# CAMERA_INTERFACE.net
KiCad netlist of a schematic drawn in Altium Designer
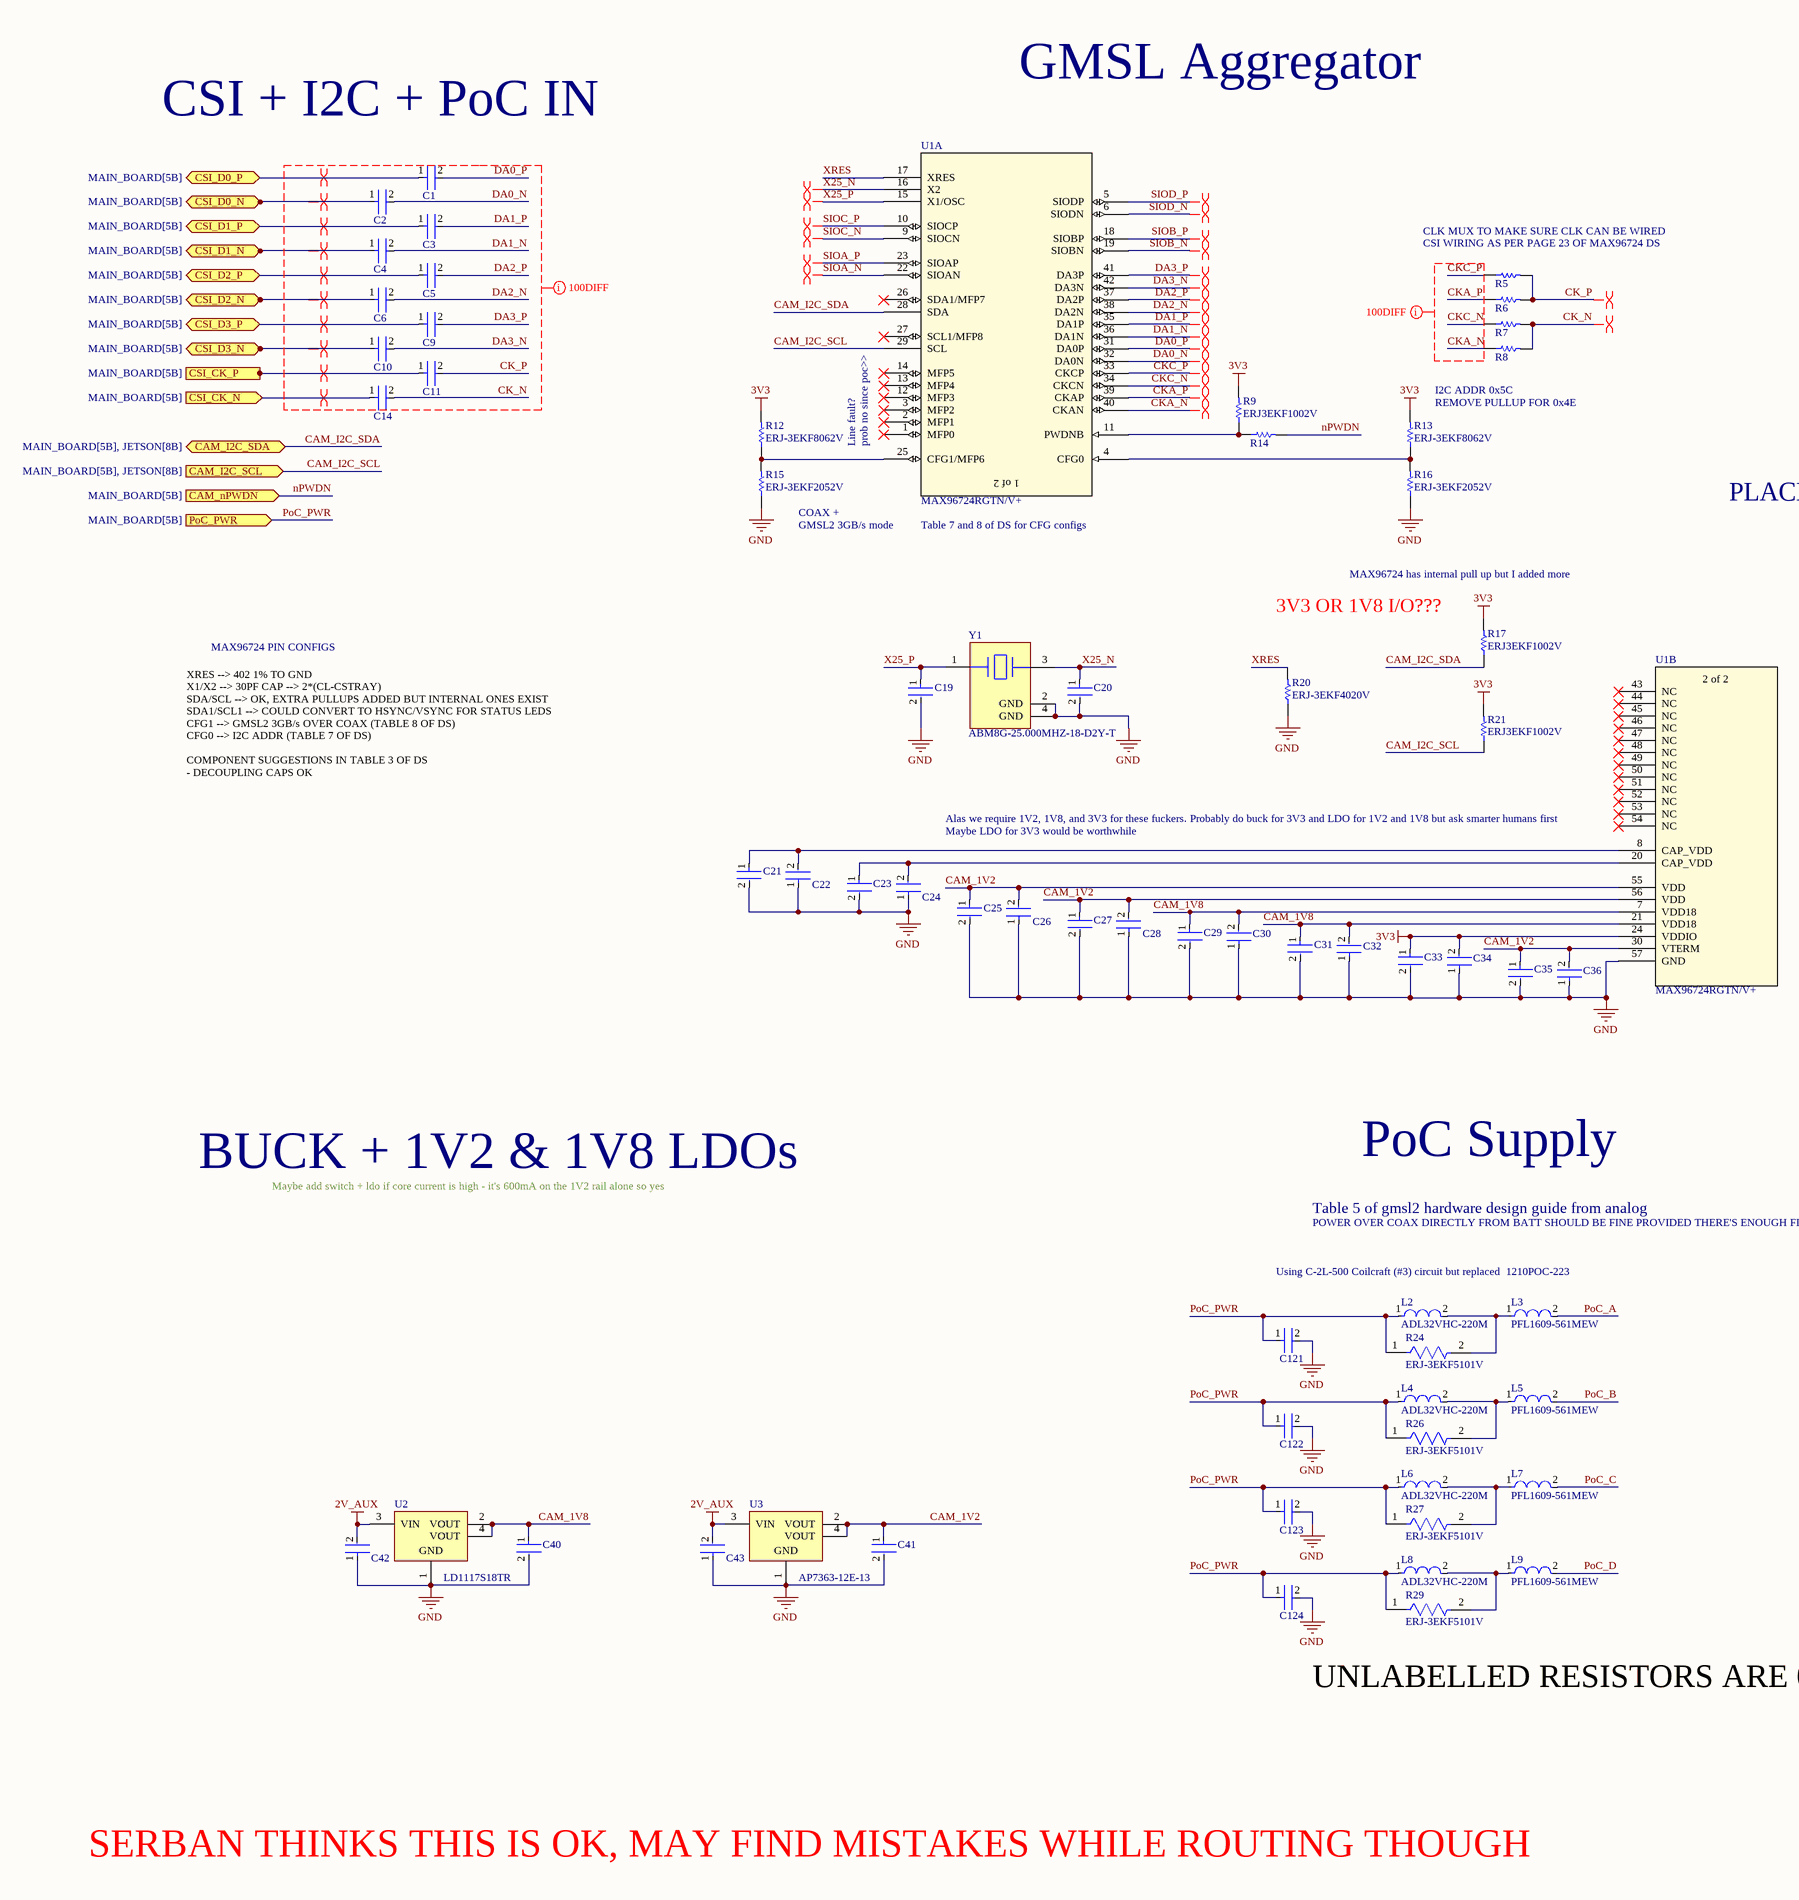
[diagram p0: CAMERA_INTERFACE.SchDoc, left]
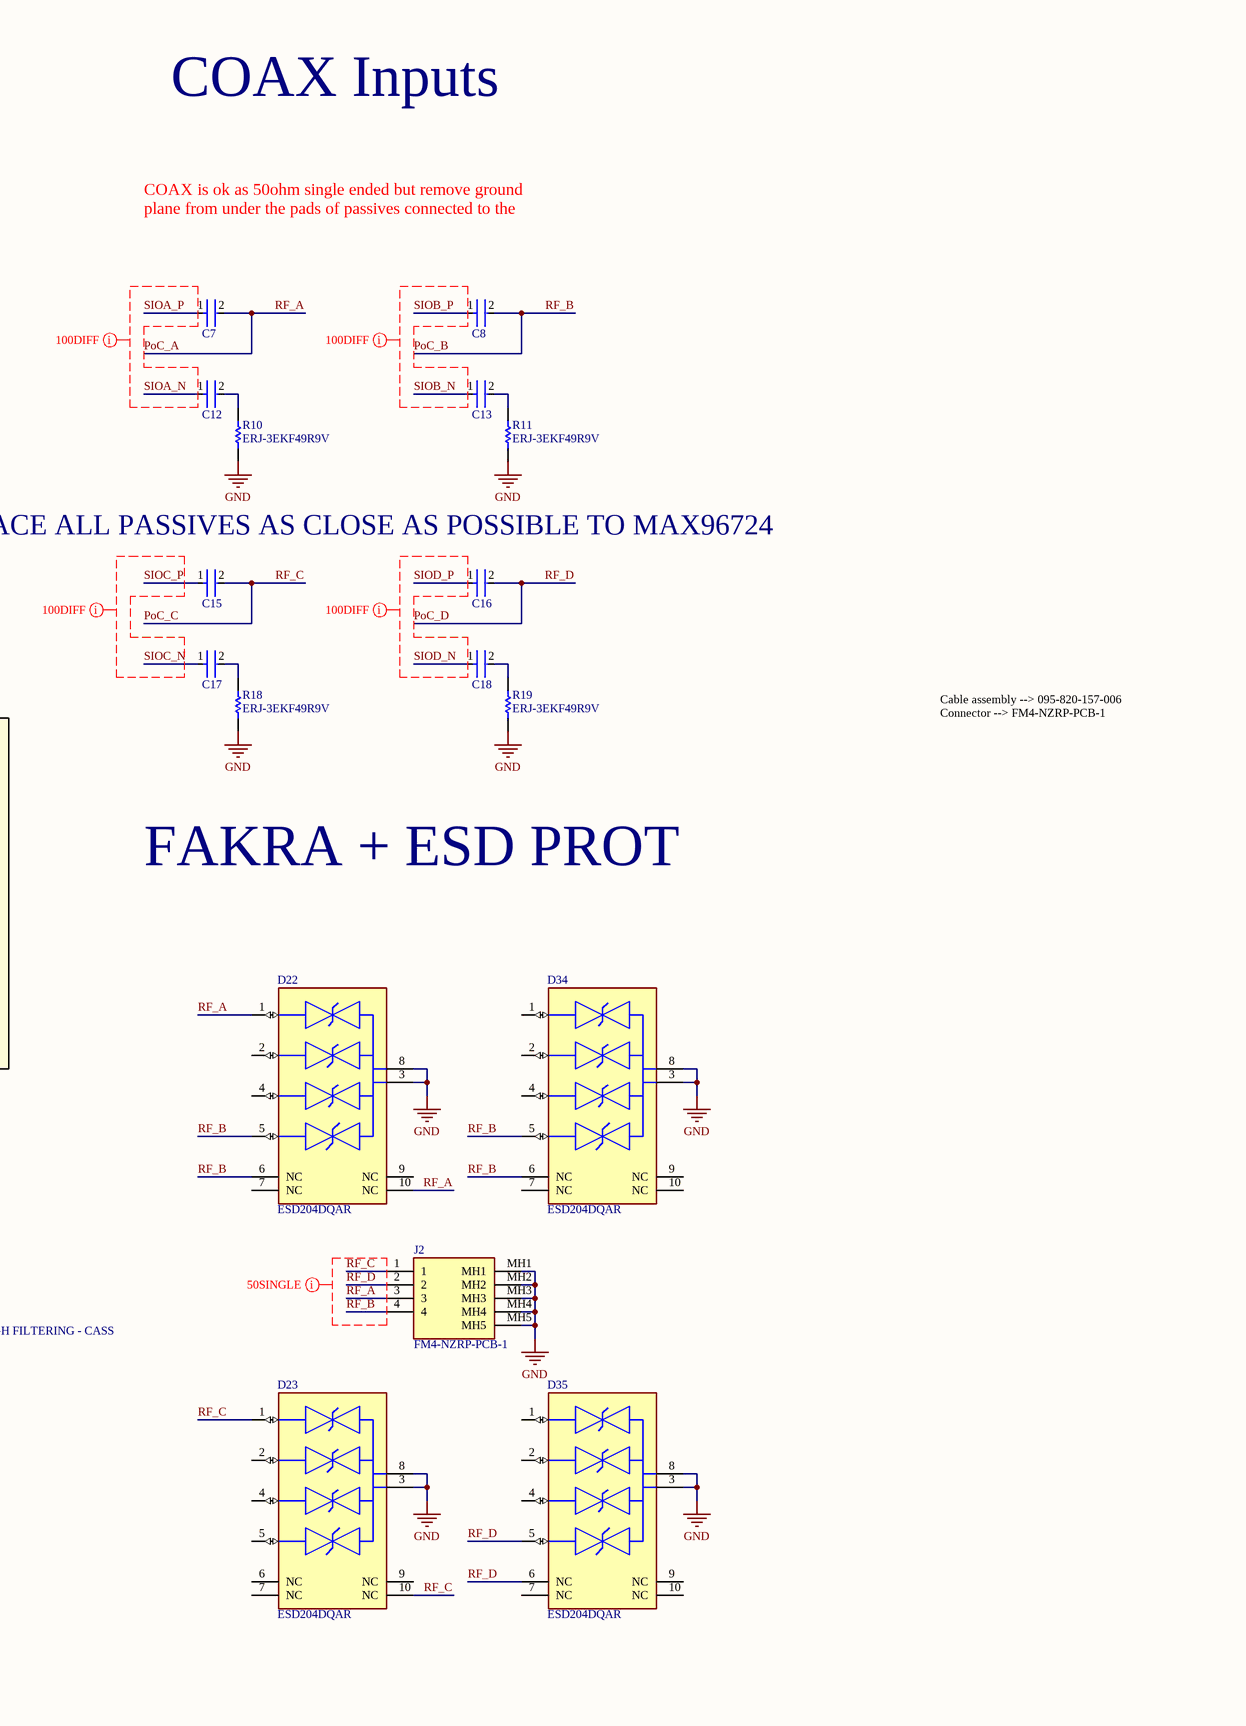
[diagram p1: CAMERA_INTERFACE.SchDoc, right]

(export (version "E")
  (design (tool "Eeschema 10.0.6"))
  (components
    (comp (ref "C1")
      (value "C1005X7R1H104K050BB")
      (footprint "FP-C1005-050-0_05-IPC_C")
      (description "Multilayer Ceramic Capacitors 100nF ±10% 50V X7R SMD 0402")
      (fields (field (name "VOLTAGE") "50V") (field (name "TOLERANCE") "10%"))
      (libsource (lib "Altium Content Vault") (part "b4654b650e69147ec39a6b967a45e02"))
    )
    (comp (ref "C2")
      (value "C1005X7R1H104K050BB")
      (footprint "FP-C1005-050-0_05-IPC_C")
      (description "Multilayer Ceramic Capacitors 100nF ±10% 50V X7R SMD 0402")
      (fields (field (name "VOLTAGE") "50V") (field (name "TOLERANCE") "10%"))
      (libsource (lib "Altium Content Vault") (part "b4654b650e69147ec39a6b967a45e02"))
    )
    (comp (ref "C3")
      (value "C1005X7R1H104K050BB")
      (footprint "FP-C1005-050-0_05-IPC_C")
      (description "Multilayer Ceramic Capacitors 100nF ±10% 50V X7R SMD 0402")
      (fields (field (name "VOLTAGE") "50V") (field (name "TOLERANCE") "10%"))
      (libsource (lib "Altium Content Vault") (part "b4654b650e69147ec39a6b967a45e02"))
    )
    (comp (ref "C4")
      (value "C1005X7R1H104K050BB")
      (footprint "FP-C1005-050-0_05-IPC_C")
      (description "Multilayer Ceramic Capacitors 100nF ±10% 50V X7R SMD 0402")
      (fields (field (name "VOLTAGE") "50V") (field (name "TOLERANCE") "10%"))
      (libsource (lib "Altium Content Vault") (part "b4654b650e69147ec39a6b967a45e02"))
    )
    (comp (ref "C5")
      (value "C1005X7R1H104K050BB")
      (footprint "FP-C1005-050-0_05-IPC_C")
      (description "Multilayer Ceramic Capacitors 100nF ±10% 50V X7R SMD 0402")
      (fields (field (name "VOLTAGE") "50V") (field (name "TOLERANCE") "10%"))
      (libsource (lib "Altium Content Vault") (part "b4654b650e69147ec39a6b967a45e02"))
    )
    (comp (ref "C6")
      (value "C1005X7R1H104K050BB")
      (footprint "FP-C1005-050-0_05-IPC_C")
      (description "Multilayer Ceramic Capacitors 100nF ±10% 50V X7R SMD 0402")
      (fields (field (name "VOLTAGE") "50V") (field (name "TOLERANCE") "10%"))
      (libsource (lib "Altium Content Vault") (part "b4654b650e69147ec39a6b967a45e02"))
    )
    (comp (ref "C7")
      (value "C1005X7R1H104K050BB")
      (footprint "FP-C1005-050-0_05-IPC_C")
      (description "Multilayer Ceramic Capacitors 100nF ±10% 50V X7R SMD 0402")
      (fields (field (name "VOLTAGE") "50V") (field (name "TOLERANCE") "10%"))
      (libsource (lib "Altium Content Vault") (part "b4654b650e69147ec39a6b967a45e02"))
    )
    (comp (ref "C8")
      (value "C1005X7R1H104K050BB")
      (footprint "FP-C1005-050-0_05-IPC_C")
      (description "Multilayer Ceramic Capacitors 100nF ±10% 50V X7R SMD 0402")
      (fields (field (name "VOLTAGE") "50V") (field (name "TOLERANCE") "10%"))
      (libsource (lib "Altium Content Vault") (part "b4654b650e69147ec39a6b967a45e02"))
    )
    (comp (ref "C9")
      (value "C1005X7R1H104K050BB")
      (footprint "FP-C1005-050-0_05-IPC_C")
      (description "Multilayer Ceramic Capacitors 100nF ±10% 50V X7R SMD 0402")
      (fields (field (name "VOLTAGE") "50V") (field (name "TOLERANCE") "10%"))
      (libsource (lib "Altium Content Vault") (part "b4654b650e69147ec39a6b967a45e02"))
    )
    (comp (ref "C10")
      (value "C1005X7R1H104K050BB")
      (footprint "FP-C1005-050-0_05-IPC_C")
      (description "Multilayer Ceramic Capacitors 100nF ±10% 50V X7R SMD 0402")
      (fields (field (name "VOLTAGE") "50V") (field (name "TOLERANCE") "10%"))
      (libsource (lib "Altium Content Vault") (part "b4654b650e69147ec39a6b967a45e02"))
    )
    (comp (ref "C11")
      (value "C1005X7R1H104K050BB")
      (footprint "FP-C1005-050-0_05-IPC_C")
      (description "Multilayer Ceramic Capacitors 100nF ±10% 50V X7R SMD 0402")
      (fields (field (name "VOLTAGE") "50V") (field (name "TOLERANCE") "10%"))
      (libsource (lib "Altium Content Vault") (part "b4654b650e69147ec39a6b967a45e02"))
    )
    (comp (ref "C12")
      (value "C1005X7R1H104K050BB")
      (footprint "FP-C1005-050-0_05-IPC_C")
      (description "Multilayer Ceramic Capacitors 100nF ±10% 50V X7R SMD 0402")
      (fields (field (name "VOLTAGE") "50V") (field (name "TOLERANCE") "10%"))
      (libsource (lib "Altium Content Vault") (part "b4654b650e69147ec39a6b967a45e02"))
    )
    (comp (ref "C13")
      (value "C1005X7R1H104K050BB")
      (footprint "FP-C1005-050-0_05-IPC_C")
      (description "Multilayer Ceramic Capacitors 100nF ±10% 50V X7R SMD 0402")
      (fields (field (name "VOLTAGE") "50V") (field (name "TOLERANCE") "10%"))
      (libsource (lib "Altium Content Vault") (part "b4654b650e69147ec39a6b967a45e02"))
    )
    (comp (ref "C14")
      (value "C1005X7R1H104K050BB")
      (footprint "FP-C1005-050-0_05-IPC_C")
      (description "Multilayer Ceramic Capacitors 100nF ±10% 50V X7R SMD 0402")
      (fields (field (name "VOLTAGE") "50V") (field (name "TOLERANCE") "10%"))
      (libsource (lib "Altium Content Vault") (part "b4654b650e69147ec39a6b967a45e02"))
    )
    (comp (ref "C15")
      (value "C1005X7R1H104K050BB")
      (footprint "FP-C1005-050-0_05-IPC_C")
      (description "Multilayer Ceramic Capacitors 100nF ±10% 50V X7R SMD 0402")
      (fields (field (name "VOLTAGE") "50V") (field (name "TOLERANCE") "10%"))
      (libsource (lib "Altium Content Vault") (part "b4654b650e69147ec39a6b967a45e02"))
    )
    (comp (ref "C16")
      (value "C1005X7R1H104K050BB")
      (footprint "FP-C1005-050-0_05-IPC_C")
      (description "Multilayer Ceramic Capacitors 100nF ±10% 50V X7R SMD 0402")
      (fields (field (name "VOLTAGE") "50V") (field (name "TOLERANCE") "10%"))
      (libsource (lib "Altium Content Vault") (part "b4654b650e69147ec39a6b967a45e02"))
    )
    (comp (ref "C17")
      (value "C1005X7R1H104K050BB")
      (footprint "FP-C1005-050-0_05-IPC_C")
      (description "Multilayer Ceramic Capacitors 100nF ±10% 50V X7R SMD 0402")
      (fields (field (name "VOLTAGE") "50V") (field (name "TOLERANCE") "10%"))
      (libsource (lib "Altium Content Vault") (part "b4654b650e69147ec39a6b967a45e02"))
    )
    (comp (ref "C18")
      (value "C1005X7R1H104K050BB")
      (footprint "FP-C1005-050-0_05-IPC_C")
      (description "Multilayer Ceramic Capacitors 100nF ±10% 50V X7R SMD 0402")
      (fields (field (name "VOLTAGE") "50V") (field (name "TOLERANCE") "10%"))
      (libsource (lib "Altium Content Vault") (part "b4654b650e69147ec39a6b967a45e02"))
    )
    (comp (ref "C19")
      (value "C0603C300J5GACTU")
      (footprint "FP-C0603C-CF-MFG")
      (description "CAP CER 30PF 50V 5% NP0 0603")
      (fields
        (field (name "MANUFACTURER") "KEMET")
        (field (name "OCTOPART") "https://octopart.com/c0603c300j5gactu-kemet-199455")
      )
      (libsource (lib "Altium Content Vault") (part "b4654b650e69147ec39a6b967a45e02"))
    )
    (comp (ref "C20")
      (value "C0603C300J5GACTU")
      (footprint "FP-C0603C-CF-MFG")
      (description "CAP CER 30PF 50V 5% NP0 0603")
      (fields
        (field (name "MANUFACTURER") "KEMET")
        (field (name "OCTOPART") "https://octopart.com/c0603c300j5gactu-kemet-199455")
      )
      (libsource (lib "Altium Content Vault") (part "b4654b650e69147ec39a6b967a45e02"))
    )
    (comp (ref "C21")
      (value "CL05A106MP5NUNC")
      (footprint "FP-CL05A106MP5NUNC-MFG")
      (description "CAP CER 10UF 10V X5R 0402")
      (fields
        (field (name "OCTOPART") "https://octopart.com/cl05a106mp5nunc-samsung-22457395")
        (field (name "TOLERANCE") "20%")
      )
      (libsource (lib "Altium Content Vault") (part "b4654b650e69147ec39a6b967a45e02"))
    )
    (comp (ref "C22")
      (value "C1005X7R1H104K050BB")
      (footprint "FP-C1005-050-0_05-IPC_C")
      (description "Multilayer Ceramic Capacitors 100nF ±10% 50V X7R SMD 0402")
      (fields (field (name "VOLTAGE") "50V") (field (name "TOLERANCE") "10%"))
      (libsource (lib "Altium Content Vault") (part "b4654b650e69147ec39a6b967a45e02"))
    )
    (comp (ref "C23")
      (value "CL05A106MP5NUNC")
      (footprint "FP-CL05A106MP5NUNC-MFG")
      (description "CAP CER 10UF 10V X5R 0402")
      (fields
        (field (name "OCTOPART") "https://octopart.com/cl05a106mp5nunc-samsung-22457395")
        (field (name "TOLERANCE") "20%")
      )
      (libsource (lib "Altium Content Vault") (part "b4654b650e69147ec39a6b967a45e02"))
    )
    (comp (ref "C24")
      (value "C1005X7R1H104K050BB")
      (footprint "FP-C1005-050-0_05-IPC_C")
      (description "Multilayer Ceramic Capacitors 100nF ±10% 50V X7R SMD 0402")
      (fields (field (name "VOLTAGE") "50V") (field (name "TOLERANCE") "10%"))
      (libsource (lib "Altium Content Vault") (part "b4654b650e69147ec39a6b967a45e02"))
    )
    (comp (ref "C25")
      (value "CL05A106MP5NUNC")
      (footprint "FP-CL05A106MP5NUNC-MFG")
      (description "CAP CER 10UF 10V X5R 0402")
      (fields
        (field (name "OCTOPART") "https://octopart.com/cl05a106mp5nunc-samsung-22457395")
        (field (name "TOLERANCE") "20%")
      )
      (libsource (lib "Altium Content Vault") (part "b4654b650e69147ec39a6b967a45e02"))
    )
    (comp (ref "C26")
      (value "C1005X7R1H104K050BB")
      (footprint "FP-C1005-050-0_05-IPC_C")
      (description "Multilayer Ceramic Capacitors 100nF ±10% 50V X7R SMD 0402")
      (fields (field (name "VOLTAGE") "50V") (field (name "TOLERANCE") "10%"))
      (libsource (lib "Altium Content Vault") (part "b4654b650e69147ec39a6b967a45e02"))
    )
    (comp (ref "C27")
      (value "CL05A106MP5NUNC")
      (footprint "FP-CL05A106MP5NUNC-MFG")
      (description "CAP CER 10UF 10V X5R 0402")
      (fields
        (field (name "OCTOPART") "https://octopart.com/cl05a106mp5nunc-samsung-22457395")
        (field (name "TOLERANCE") "20%")
      )
      (libsource (lib "Altium Content Vault") (part "b4654b650e69147ec39a6b967a45e02"))
    )
    (comp (ref "C28")
      (value "C1005X7R1H104K050BB")
      (footprint "FP-C1005-050-0_05-IPC_C")
      (description "Multilayer Ceramic Capacitors 100nF ±10% 50V X7R SMD 0402")
      (fields (field (name "VOLTAGE") "50V") (field (name "TOLERANCE") "10%"))
      (libsource (lib "Altium Content Vault") (part "b4654b650e69147ec39a6b967a45e02"))
    )
    (comp (ref "C29")
      (value "CL05A106MP5NUNC")
      (footprint "FP-CL05A106MP5NUNC-MFG")
      (description "CAP CER 10UF 10V X5R 0402")
      (fields
        (field (name "OCTOPART") "https://octopart.com/cl05a106mp5nunc-samsung-22457395")
        (field (name "TOLERANCE") "20%")
      )
      (libsource (lib "Altium Content Vault") (part "b4654b650e69147ec39a6b967a45e02"))
    )
    (comp (ref "C30")
      (value "C0402C103M5RACTU")
      (footprint "FP-C0402-BB-MFG")
      (description "CAP CER 10000PF 50V 20% X7R 0402")
      (fields
        (field (name "TOLERANCE") "0.2")
        (field (name "OCTOPART") "https://octopart.com/c0402c103m5ractu-kemet-17125571")
      )
      (libsource (lib "Altium Content Vault") (part "b4654b650e69147ec39a6b967a45e02"))
    )
    (comp (ref "C31")
      (value "CL05A106MP5NUNC")
      (footprint "FP-CL05A106MP5NUNC-MFG")
      (description "CAP CER 10UF 10V X5R 0402")
      (fields
        (field (name "OCTOPART") "https://octopart.com/cl05a106mp5nunc-samsung-22457395")
        (field (name "TOLERANCE") "20%")
      )
      (libsource (lib "Altium Content Vault") (part "b4654b650e69147ec39a6b967a45e02"))
    )
    (comp (ref "C32")
      (value "C0402C103M5RACTU")
      (footprint "FP-C0402-BB-MFG")
      (description "CAP CER 10000PF 50V 20% X7R 0402")
      (fields
        (field (name "TOLERANCE") "0.2")
        (field (name "OCTOPART") "https://octopart.com/c0402c103m5ractu-kemet-17125571")
      )
      (libsource (lib "Altium Content Vault") (part "b4654b650e69147ec39a6b967a45e02"))
    )
    (comp (ref "C33")
      (value "CL05A106MP5NUNC")
      (footprint "FP-CL05A106MP5NUNC-MFG")
      (description "CAP CER 10UF 10V X5R 0402")
      (fields
        (field (name "OCTOPART") "https://octopart.com/cl05a106mp5nunc-samsung-22457395")
        (field (name "TOLERANCE") "20%")
      )
      (libsource (lib "Altium Content Vault") (part "b4654b650e69147ec39a6b967a45e02"))
    )
    (comp (ref "C34")
      (value "C0402C103M5RACTU")
      (footprint "FP-C0402-BB-MFG")
      (description "CAP CER 10000PF 50V 20% X7R 0402")
      (fields
        (field (name "TOLERANCE") "0.2")
        (field (name "OCTOPART") "https://octopart.com/c0402c103m5ractu-kemet-17125571")
      )
      (libsource (lib "Altium Content Vault") (part "b4654b650e69147ec39a6b967a45e02"))
    )
    (comp (ref "C35")
      (value "CL05A106MP5NUNC")
      (footprint "FP-CL05A106MP5NUNC-MFG")
      (description "CAP CER 10UF 10V X5R 0402")
      (fields
        (field (name "OCTOPART") "https://octopart.com/cl05a106mp5nunc-samsung-22457395")
        (field (name "TOLERANCE") "20%")
      )
      (libsource (lib "Altium Content Vault") (part "b4654b650e69147ec39a6b967a45e02"))
    )
    (comp (ref "C36")
      (value "C0402C103M5RACTU")
      (footprint "FP-C0402-BB-MFG")
      (description "CAP CER 10000PF 50V 20% X7R 0402")
      (fields
        (field (name "TOLERANCE") "0.2")
        (field (name "OCTOPART") "https://octopart.com/c0402c103m5ractu-kemet-17125571")
      )
      (libsource (lib "Altium Content Vault") (part "b4654b650e69147ec39a6b967a45e02"))
    )
    (comp (ref "C40")
      (value "GRM188R60J106ME47D")
      (footprint "FP-GRM188-0_1-e0_2_0_55-IPC_A")
      (description "Chip Multilayer Ceramic Capacitors for General Purpose, 0603, 10uF, X5R, 15%, 20%, 6.3V")
      (fields (field (name "VOLTAGE") "6.3V") (field (name "TOLERANCE") "20%"))
      (libsource (lib "Altium Content Vault") (part "02cd4be3c70576c341d710602a673aa"))
    )
    (comp (ref "C41")
      (value "GRM188R60J106ME47D")
      (footprint "FP-GRM188-0_1-e0_2_0_55-IPC_A")
      (description "Chip Multilayer Ceramic Capacitors for General Purpose, 0603, 10uF, X5R, 15%, 20%, 6.3V")
      (fields (field (name "VOLTAGE") "6.3V") (field (name "TOLERANCE") "20%"))
      (libsource (lib "Altium Content Vault") (part "02cd4be3c70576c341d710602a673aa"))
    )
    (comp (ref "C42")
      (value "C1005X7R1H104K050BB")
      (footprint "FP-C1005-050-0_05-IPC_C")
      (description "Multilayer Ceramic Capacitors 100nF ±10% 50V X7R SMD 0402")
      (fields (field (name "VOLTAGE") "50V") (field (name "TOLERANCE") "10%"))
      (libsource (lib "Altium Content Vault") (part "b4654b650e69147ec39a6b967a45e02"))
    )
    (comp (ref "C43")
      (value "C1005X7R1H104K050BB")
      (footprint "FP-C1005-050-0_05-IPC_C")
      (description "Multilayer Ceramic Capacitors 100nF ±10% 50V X7R SMD 0402")
      (fields (field (name "VOLTAGE") "50V") (field (name "TOLERANCE") "10%"))
      (libsource (lib "Altium Content Vault") (part "b4654b650e69147ec39a6b967a45e02"))
    )
    (comp (ref "C121")
      (value "GRM21BR61E226ME44L")
      (footprint "FP-GRM21B-0_2-e0_2_0_7-IPC_B")
      (description "Chip Multilayer Ceramic Capacitors for General Purpose, 0805, 22uF, X5R, 15%, 20%, 25V")
      (fields (field (name "TOLERANCE") "20%") (field (name "VOLTAGE") "25V"))
      (libsource (lib "Altium Content Vault") (part "b4654b650e69147ec39a6b967a45e02"))
    )
    (comp (ref "C122")
      (value "GRM21BR61E226ME44L")
      (footprint "FP-GRM21B-0_2-e0_2_0_7-IPC_B")
      (description "Chip Multilayer Ceramic Capacitors for General Purpose, 0805, 22uF, X5R, 15%, 20%, 25V")
      (fields (field (name "TOLERANCE") "20%") (field (name "VOLTAGE") "25V"))
      (libsource (lib "Altium Content Vault") (part "b4654b650e69147ec39a6b967a45e02"))
    )
    (comp (ref "C123")
      (value "GRM21BR61E226ME44L")
      (footprint "FP-GRM21B-0_2-e0_2_0_7-IPC_B")
      (description "Chip Multilayer Ceramic Capacitors for General Purpose, 0805, 22uF, X5R, 15%, 20%, 25V")
      (fields (field (name "TOLERANCE") "20%") (field (name "VOLTAGE") "25V"))
      (libsource (lib "Altium Content Vault") (part "b4654b650e69147ec39a6b967a45e02"))
    )
    (comp (ref "C124")
      (value "GRM21BR61E226ME44L")
      (footprint "FP-GRM21B-0_2-e0_2_0_7-IPC_B")
      (description "Chip Multilayer Ceramic Capacitors for General Purpose, 0805, 22uF, X5R, 15%, 20%, 25V")
      (fields (field (name "TOLERANCE") "20%") (field (name "VOLTAGE") "25V"))
      (libsource (lib "Altium Content Vault") (part "b4654b650e69147ec39a6b967a45e02"))
    )
    (comp (ref "D22")
      (value "ESD204DQAR")
      (footprint "FP-DQA0010A-MFG")
      (description "4-CHANNEL LOW-CAPACITANCE SURGE")
      (fields
        (field (name "MANUFACTURER") "Texas Instruments")
        (field (name "OCTOPART") "https://octopart.com/esd204dqar-texas+instruments-89917476")
      )
      (libsource (lib "Altium Content Vault") (part "1465e58c1818c7767b55926832f0bf5"))
    )
    (comp (ref "D23")
      (value "ESD204DQAR")
      (footprint "FP-DQA0010A-MFG")
      (description "4-CHANNEL LOW-CAPACITANCE SURGE")
      (fields
        (field (name "MANUFACTURER") "Texas Instruments")
        (field (name "OCTOPART") "https://octopart.com/esd204dqar-texas+instruments-89917476")
      )
      (libsource (lib "Altium Content Vault") (part "1465e58c1818c7767b55926832f0bf5"))
    )
    (comp (ref "D34")
      (value "ESD204DQAR")
      (footprint "FP-DQA0010A-MFG")
      (description "4-CHANNEL LOW-CAPACITANCE SURGE")
      (fields
        (field (name "MANUFACTURER") "Texas Instruments")
        (field (name "OCTOPART") "https://octopart.com/esd204dqar-texas+instruments-89917476")
      )
      (libsource (lib "Altium Content Vault") (part "1465e58c1818c7767b55926832f0bf5"))
    )
    (comp (ref "D35")
      (value "ESD204DQAR")
      (footprint "FP-DQA0010A-MFG")
      (description "4-CHANNEL LOW-CAPACITANCE SURGE")
      (fields
        (field (name "MANUFACTURER") "Texas Instruments")
        (field (name "OCTOPART") "https://octopart.com/esd204dqar-texas+instruments-89917476")
      )
      (libsource (lib "Altium Content Vault") (part "1465e58c1818c7767b55926832f0bf5"))
    )
    (comp (ref "J2")
      (value "FM4-NZRP-PCB-1")
      (footprint "FM4-NZRP-PCB-1-Footprint-1")
      (description "Connector RF Mini-FAKRA Plug 9GHz 50Ohm Solder Right Angle Through Hole")
      (libsource (lib "uORocketry Hardware") (part "FM4-NZRP-PCB-1"))
    )
    (comp (ref "L2")
      (value "ADL32VHC-220M")
      (footprint "FP-1210POC-MFG")
      (description "NOT COILCRAFT - ACTUAL P# --> ADL32VHC-220M\r\n - Power Injection Chokes for PoC")
      (fields
        (field (name "MANUFACTURER") "coilcraft")
        (field (name "OCTOPART") "https://octopart.com/1210poc-223mrc-coilcraft-103207315")
      )
      (libsource (lib "Altium Content Vault") (part "725321dda6339637d4d059423bc1c3c"))
    )
    (comp (ref "L3")
      (value "PFL1609-561MEW")
      (footprint "FP-PFL1609-MFG")
      (description "Fixed Inductors PFL1609 Low Profile 0.56 uH 20 % 1.4 A")
      (fields (field (name "MANUFACTURER") "coilcraft") (field (name "TOLERANCE") "20%"))
      (libsource (lib "Altium Content Vault") (part "725321dda6339637d4d059423bc1c3c"))
    )
    (comp (ref "L4")
      (value "ADL32VHC-220M")
      (footprint "FP-1210POC-MFG")
      (description "NOT COILCRAFT - ACTUAL P# --> ADL32VHC-220M\r\n - Power Injection Chokes for PoC")
      (fields
        (field (name "MANUFACTURER") "coilcraft")
        (field (name "OCTOPART") "https://octopart.com/1210poc-223mrc-coilcraft-103207315")
      )
      (libsource (lib "Altium Content Vault") (part "725321dda6339637d4d059423bc1c3c"))
    )
    (comp (ref "L5")
      (value "PFL1609-561MEW")
      (footprint "FP-PFL1609-MFG")
      (description "Fixed Inductors PFL1609 Low Profile 0.56 uH 20 % 1.4 A")
      (fields (field (name "MANUFACTURER") "coilcraft") (field (name "TOLERANCE") "20%"))
      (libsource (lib "Altium Content Vault") (part "725321dda6339637d4d059423bc1c3c"))
    )
    (comp (ref "L6")
      (value "ADL32VHC-220M")
      (footprint "FP-1210POC-MFG")
      (description "NOT COILCRAFT - ACTUAL P# --> ADL32VHC-220M\r\n - Power Injection Chokes for PoC")
      (fields
        (field (name "MANUFACTURER") "coilcraft")
        (field (name "OCTOPART") "https://octopart.com/1210poc-223mrc-coilcraft-103207315")
      )
      (libsource (lib "Altium Content Vault") (part "725321dda6339637d4d059423bc1c3c"))
    )
    (comp (ref "L7")
      (value "PFL1609-561MEW")
      (footprint "FP-PFL1609-MFG")
      (description "Fixed Inductors PFL1609 Low Profile 0.56 uH 20 % 1.4 A")
      (fields (field (name "MANUFACTURER") "coilcraft") (field (name "TOLERANCE") "20%"))
      (libsource (lib "Altium Content Vault") (part "725321dda6339637d4d059423bc1c3c"))
    )
    (comp (ref "L8")
      (value "ADL32VHC-220M")
      (footprint "FP-1210POC-MFG")
      (description "NOT COILCRAFT - ACTUAL P# --> ADL32VHC-220M\r\n - Power Injection Chokes for PoC")
      (fields
        (field (name "MANUFACTURER") "coilcraft")
        (field (name "OCTOPART") "https://octopart.com/1210poc-223mrc-coilcraft-103207315")
      )
      (libsource (lib "Altium Content Vault") (part "725321dda6339637d4d059423bc1c3c"))
    )
    (comp (ref "L9")
      (value "PFL1609-561MEW")
      (footprint "FP-PFL1609-MFG")
      (description "Fixed Inductors PFL1609 Low Profile 0.56 uH 20 % 1.4 A")
      (fields (field (name "MANUFACTURER") "coilcraft") (field (name "TOLERANCE") "20%"))
      (libsource (lib "Altium Content Vault") (part "725321dda6339637d4d059423bc1c3c"))
    )
    (comp (ref "R5")
      (value "0402 JUMPER 0 OHM")
      (footprint "RESC1005X40X25NL05T05")
      (description "READ THE NAME")
      (libsource (lib "uORocketry Hardware") (part "RES"))
    )
    (comp (ref "R6")
      (value "0402 JUMPER 0 OHM")
      (footprint "RESC1005X40X25NL05T05")
      (description "READ THE NAME")
      (libsource (lib "uORocketry Hardware") (part "RES"))
    )
    (comp (ref "R7")
      (value "0402 JUMPER 0 OHM")
      (footprint "RESC1005X40X25NL05T05")
      (description "READ THE NAME")
      (libsource (lib "uORocketry Hardware") (part "RES"))
    )
    (comp (ref "R8")
      (value "0402 JUMPER 0 OHM")
      (footprint "RESC1005X40X25NL05T05")
      (description "READ THE NAME")
      (libsource (lib "uORocketry Hardware") (part "RES"))
    )
    (comp (ref "R9")
      (value "ERJ3EKF1002V")
      (footprint "RESC1609X55X30LL15T15")
      (description "Chip Resistor, 10 KOhm, +/- 1%, 0.1 W, -55 to 155 degC, 0603 (1608 Metric), RoHS, Tape and Reel")
      (fields (field (name "TOLERANCE") "1%") (field (name "MANUFACTURER") "Panasonic"))
      (libsource (lib "Altium Content Vault") (part "RES-2"))
    )
    (comp (ref "R10")
      (value "ERJ-3EKF49R9V")
      (footprint "RESC1608X55X30ML15T15")
      (fields (field (name "MANUFACTURER") "Panasonic"))
      (libsource (lib "Altium Content Vault") (part "RES"))
    )
    (comp (ref "R11")
      (value "ERJ-3EKF49R9V")
      (footprint "RESC1608X55X30ML15T15")
      (fields (field (name "MANUFACTURER") "Panasonic"))
      (libsource (lib "Altium Content Vault") (part "RES"))
    )
    (comp (ref "R12")
      (value "ERJ-3EKF8062V")
      (footprint "RESC1608X55X30LL15T15")
      (fields (field (name "MANUFACTURER") "Panasonic"))
      (libsource (lib "Altium Content Vault") (part "RES"))
    )
    (comp (ref "R13")
      (value "ERJ-3EKF8062V")
      (footprint "RESC1608X55X30LL15T15")
      (fields (field (name "MANUFACTURER") "Panasonic"))
      (libsource (lib "Altium Content Vault") (part "RES"))
    )
    (comp (ref "R14")
      (value "0402 JUMPER 0 OHM")
      (footprint "RESC1005X40X25NL05T05")
      (description "READ THE NAME")
      (libsource (lib "uORocketry Hardware") (part "RES"))
    )
    (comp (ref "R15")
      (value "ERJ-3EKF2052V")
      (footprint "RESC1608X55X30NL15T15")
      (fields (field (name "MANUFACTURER") "Panasonic"))
      (libsource (lib "Altium Content Vault") (part "RES"))
    )
    (comp (ref "R16")
      (value "ERJ-3EKF2052V")
      (footprint "RESC1608X55X30NL15T15")
      (fields (field (name "MANUFACTURER") "Panasonic"))
      (libsource (lib "Altium Content Vault") (part "RES"))
    )
    (comp (ref "R17")
      (value "ERJ3EKF1002V")
      (footprint "RESC1609X55X30LL15T15")
      (description "Chip Resistor, 10 KOhm, +/- 1%, 0.1 W, -55 to 155 degC, 0603 (1608 Metric), RoHS, Tape and Reel")
      (fields (field (name "TOLERANCE") "1%") (field (name "MANUFACTURER") "Panasonic"))
      (libsource (lib "Altium Content Vault") (part "RES-2"))
    )
    (comp (ref "R18")
      (value "ERJ-3EKF49R9V")
      (footprint "RESC1608X55X30ML15T15")
      (fields (field (name "MANUFACTURER") "Panasonic"))
      (libsource (lib "Altium Content Vault") (part "RES"))
    )
    (comp (ref "R19")
      (value "ERJ-3EKF49R9V")
      (footprint "RESC1608X55X30ML15T15")
      (fields (field (name "MANUFACTURER") "Panasonic"))
      (libsource (lib "Altium Content Vault") (part "RES"))
    )
    (comp (ref "R20")
      (value "ERJ-3EKF4020V")
      (footprint "RESC1608X55X30LL15T15")
      (fields (field (name "MANUFACTURER") "Panasonic"))
      (libsource (lib "Altium Content Vault") (part "RES"))
    )
    (comp (ref "R21")
      (value "ERJ3EKF1002V")
      (footprint "RESC1609X55X30LL15T15")
      (description "Chip Resistor, 10 KOhm, +/- 1%, 0.1 W, -55 to 155 degC, 0603 (1608 Metric), RoHS, Tape and Reel")
      (fields (field (name "TOLERANCE") "1%") (field (name "MANUFACTURER") "Panasonic"))
      (libsource (lib "Altium Content Vault") (part "RES-2"))
    )
    (comp (ref "R24")
      (value "ERJ-3EKF5101V")
      (footprint "FP-ERJ3EK-MFG")
      (description "RES SMD 5.1K OHM 1% 1/10W 0603")
      (fields (field (name "TOLERANCE") "1%"))
      (libsource (lib "Altium Content Vault") (part "1029c3af85768c4190bb7ad29bc67b5"))
    )
    (comp (ref "R26")
      (value "ERJ-3EKF5101V")
      (footprint "FP-ERJ3EK-MFG")
      (description "RES SMD 5.1K OHM 1% 1/10W 0603")
      (fields (field (name "TOLERANCE") "1%"))
      (libsource (lib "Altium Content Vault") (part "1029c3af85768c4190bb7ad29bc67b5"))
    )
    (comp (ref "R27")
      (value "ERJ-3EKF5101V")
      (footprint "FP-ERJ3EK-MFG")
      (description "RES SMD 5.1K OHM 1% 1/10W 0603")
      (fields (field (name "TOLERANCE") "1%"))
      (libsource (lib "Altium Content Vault") (part "1029c3af85768c4190bb7ad29bc67b5"))
    )
    (comp (ref "R29")
      (value "ERJ-3EKF5101V")
      (footprint "FP-ERJ3EK-MFG")
      (description "RES SMD 5.1K OHM 1% 1/10W 0603")
      (fields (field (name "TOLERANCE") "1%"))
      (libsource (lib "Altium Content Vault") (part "1029c3af85768c4190bb7ad29bc67b5"))
    )
    (comp (ref "U1")
      (value "MAX96724RGTN/V+")
      (footprint "QFN50P800X800X80_HS-57N")
      (description "Quad Tunneling GMSL2/1 to CSI-2 Deserializer")
      (libsource (lib "uORocketry Hardware") (part "MAX96724RGTN_V+-Symbol-1"))
    )
    (comp (ref "U2")
      (value "LD1117S18TR")
      (footprint "SOT-223_M")
      (description "Fixed Low Drop Positive Voltage Regulator, 1.8V, 4-Pin SOT-223, Tape and Reel")
      (libsource (lib "Altium Content Vault") (part "PM-REG-LD1117-SOT4"))
    )
    (comp (ref "U3")
      (value "AP7363-12E-13")
      (footprint "SOT-223_M")
      (description "Fixed Low Drop Positive Voltage Regulator, 1.2V (pn is for 1.5A LDO), 4-Pin SOT-223, Tape and Reel")
      (libsource (lib "Altium Content Vault") (part "PM-REG-LD1117-SOT4"))
    )
    (comp (ref "Y1")
      (value "ABM8G-25.000MHZ-18-D2Y-T")
      (footprint "FP-ABM8G-MFG")
      (description "Crystal 25MHz ±20ppm (Tol) ±30ppm (Stability) 18pF FUND 60Ω 4-Pin SMD T/R")
      (fields (field (name "TOLERANCE") "20ppm"))
      (libsource (lib "Altium Content Vault") (part "48e526d86b7f2615d98721063c72f49"))
    )
  )
  (nets
    (net (code "1") (name "/CAM_1V2") (class "Default")
      (node (ref "C25") (pin "1") (pinfunction "1_1") (pintype "passive"))
      (node (ref "C26") (pin "2") (pinfunction "2_2") (pintype "passive"))
      (node (ref "C27") (pin "1") (pinfunction "1_1") (pintype "passive"))
      (node (ref "C28") (pin "2") (pinfunction "2_2") (pintype "passive"))
      (node (ref "C35") (pin "1") (pinfunction "1_1") (pintype "passive"))
      (node (ref "C36") (pin "2") (pinfunction "2_2") (pintype "passive"))
      (node (ref "C41") (pin "1") (pinfunction "1_1") (pintype "passive"))
      (node (ref "U1") (pin "30") (pinfunction "VTERM_30") (pintype "power_in"))
      (node (ref "U1") (pin "55") (pinfunction "VDD_55") (pintype "power_in"))
      (node (ref "U1") (pin "56") (pinfunction "VDD_56") (pintype "power_in"))
      (node (ref "U3") (pin "2") (pinfunction "VOUT_2") (pintype "power_in"))
      (node (ref "U3") (pin "4") (pinfunction "VOUT_4") (pintype "power_in"))
    )
    (net (code "2") (name "/CAM_1V8") (class "Default")
      (node (ref "C29") (pin "1") (pinfunction "1_1") (pintype "passive"))
      (node (ref "C30") (pin "2") (pinfunction "2_2") (pintype "passive"))
      (node (ref "C31") (pin "1") (pinfunction "1_1") (pintype "passive"))
      (node (ref "C32") (pin "2") (pinfunction "2_2") (pintype "passive"))
      (node (ref "C40") (pin "1") (pinfunction "1_1") (pintype "passive"))
      (node (ref "U1") (pin "21") (pinfunction "VDD18_21") (pintype "power_in"))
      (node (ref "U1") (pin "7") (pinfunction "VDD18_7") (pintype "power_in"))
      (node (ref "U2") (pin "2") (pinfunction "VOUT_2") (pintype "power_in"))
      (node (ref "U2") (pin "4") (pinfunction "VOUT_4") (pintype "power_in"))
    )
    (net (code "3") (name "/CAM_I2C_SCL") (class "Default")
      (node (ref "R21") (pin "1") (pinfunction "1_1") (pintype "passive"))
      (node (ref "U1") (pin "29") (pinfunction "SCL_29") (pintype "passive"))
    )
    (net (code "4") (name "/CAM_I2C_SDA") (class "Default")
      (node (ref "R17") (pin "1") (pinfunction "1_1") (pintype "passive"))
      (node (ref "U1") (pin "28") (pinfunction "SDA_28") (pintype "passive"))
    )
    (net (code "5") (name "/CKA_N") (class "Default")
      (node (ref "R8") (pin "1") (pinfunction "1_1") (pintype "passive"))
      (node (ref "U1") (pin "40") (pinfunction "CKAN_40") (pintype "bidirectional"))
    )
    (net (code "6") (name "/CKA_P") (class "Default")
      (node (ref "R6") (pin "1") (pinfunction "1_1") (pintype "passive"))
      (node (ref "U1") (pin "39") (pinfunction "CKAP_39") (pintype "bidirectional"))
    )
    (net (code "7") (name "/CKC_N") (class "Default")
      (node (ref "R7") (pin "1") (pinfunction "1_1") (pintype "passive"))
      (node (ref "U1") (pin "34") (pinfunction "CKCN_34") (pintype "bidirectional"))
    )
    (net (code "8") (name "/CKC_P") (class "Default")
      (node (ref "R5") (pin "1") (pinfunction "1_1") (pintype "passive"))
      (node (ref "U1") (pin "33") (pinfunction "CKCP_33") (pintype "bidirectional"))
    )
    (net (code "9") (name "/CK_N") (class "Default")
      (node (ref "C14") (pin "2") (pinfunction "2_2") (pintype "passive"))
      (node (ref "R7") (pin "2") (pinfunction "2_2") (pintype "passive"))
      (node (ref "R8") (pin "2") (pinfunction "2_2") (pintype "passive"))
    )
    (net (code "10") (name "/CK_P") (class "Default")
      (node (ref "C11") (pin "2") (pinfunction "2_2") (pintype "passive"))
      (node (ref "R5") (pin "2") (pinfunction "2_2") (pintype "passive"))
      (node (ref "R6") (pin "2") (pinfunction "2_2") (pintype "passive"))
    )
    (net (code "11") (name "/CSI_CK_N") (class "Default")
      (node (ref "C14") (pin "1") (pinfunction "1_1") (pintype "passive"))
    )
    (net (code "12") (name "/CSI_CK_P") (class "Default")
      (node (ref "C11") (pin "1") (pinfunction "1_1") (pintype "passive"))
    )
    (net (code "13") (name "/CSI_D0_N") (class "Default")
      (node (ref "C2") (pin "1") (pinfunction "1_1") (pintype "passive"))
    )
    (net (code "14") (name "/CSI_D0_P") (class "Default")
      (node (ref "C1") (pin "1") (pinfunction "1_1") (pintype "passive"))
    )
    (net (code "15") (name "/CSI_D1_N") (class "Default")
      (node (ref "C4") (pin "1") (pinfunction "1_1") (pintype "passive"))
    )
    (net (code "16") (name "/CSI_D1_P") (class "Default")
      (node (ref "C3") (pin "1") (pinfunction "1_1") (pintype "passive"))
    )
    (net (code "17") (name "/CSI_D2_N") (class "Default")
      (node (ref "C6") (pin "1") (pinfunction "1_1") (pintype "passive"))
    )
    (net (code "18") (name "/CSI_D2_P") (class "Default")
      (node (ref "C5") (pin "1") (pinfunction "1_1") (pintype "passive"))
    )
    (net (code "19") (name "/CSI_D3_N") (class "Default")
      (node (ref "C10") (pin "1") (pinfunction "1_1") (pintype "passive"))
    )
    (net (code "20") (name "/CSI_D3_P") (class "Default")
      (node (ref "C9") (pin "1") (pinfunction "1_1") (pintype "passive"))
    )
    (net (code "21") (name "/DA0_N") (class "Default")
      (node (ref "C2") (pin "2") (pinfunction "2_2") (pintype "passive"))
      (node (ref "U1") (pin "32") (pinfunction "DA0N_32") (pintype "bidirectional"))
    )
    (net (code "22") (name "/DA0_P") (class "Default")
      (node (ref "C1") (pin "2") (pinfunction "2_2") (pintype "passive"))
      (node (ref "U1") (pin "31") (pinfunction "DA0P_31") (pintype "bidirectional"))
    )
    (net (code "23") (name "/DA1_N") (class "Default")
      (node (ref "C4") (pin "2") (pinfunction "2_2") (pintype "passive"))
      (node (ref "U1") (pin "36") (pinfunction "DA1N_36") (pintype "bidirectional"))
    )
    (net (code "24") (name "/DA1_P") (class "Default")
      (node (ref "C3") (pin "2") (pinfunction "2_2") (pintype "passive"))
      (node (ref "U1") (pin "35") (pinfunction "DA1P_35") (pintype "bidirectional"))
    )
    (net (code "25") (name "/DA2_N") (class "Default")
      (node (ref "C6") (pin "2") (pinfunction "2_2") (pintype "passive"))
      (node (ref "U1") (pin "38") (pinfunction "DA2N_38") (pintype "bidirectional"))
    )
    (net (code "26") (name "/DA2_P") (class "Default")
      (node (ref "C5") (pin "2") (pinfunction "2_2") (pintype "passive"))
      (node (ref "U1") (pin "37") (pinfunction "DA2P_37") (pintype "bidirectional"))
    )
    (net (code "27") (name "/DA3_N") (class "Default")
      (node (ref "C10") (pin "2") (pinfunction "2_2") (pintype "passive"))
      (node (ref "U1") (pin "42") (pinfunction "DA3N_42") (pintype "bidirectional"))
    )
    (net (code "28") (name "/DA3_P") (class "Default")
      (node (ref "C9") (pin "2") (pinfunction "2_2") (pintype "passive"))
      (node (ref "U1") (pin "41") (pinfunction "DA3P_41") (pintype "bidirectional"))
    )
    (net (code "29") (name "/PoC_A") (class "Default")
      (node (ref "C7") (pin "2") (pinfunction "2_2") (pintype "passive"))
      (node (ref "D22") (pin "1") (pinfunction "IO1_1") (pintype "bidirectional"))
      (node (ref "D22") (pin "10") (pinfunction "NC_10") (pintype "passive"))
      (node (ref "J2") (pin "3") (pinfunction "3_3") (pintype "passive"))
      (node (ref "L3") (pin "2") (pinfunction "2_2") (pintype "passive"))
    )
    (net (code "30") (name "/PoC_B") (class "Default")
      (node (ref "C8") (pin "2") (pinfunction "2_2") (pintype "passive"))
      (node (ref "D22") (pin "5") (pinfunction "IO4_5") (pintype "bidirectional"))
      (node (ref "D22") (pin "6") (pinfunction "NC_6") (pintype "passive"))
      (node (ref "D34") (pin "5") (pinfunction "IO4_5") (pintype "bidirectional"))
      (node (ref "D34") (pin "6") (pinfunction "NC_6") (pintype "passive"))
      (node (ref "J2") (pin "4") (pinfunction "4_4") (pintype "passive"))
      (node (ref "L5") (pin "2") (pinfunction "2_2") (pintype "passive"))
    )
    (net (code "31") (name "/PoC_C") (class "Default")
      (node (ref "C15") (pin "2") (pinfunction "2_2") (pintype "passive"))
      (node (ref "D23") (pin "1") (pinfunction "IO1_1") (pintype "bidirectional"))
      (node (ref "D23") (pin "10") (pinfunction "NC_10") (pintype "passive"))
      (node (ref "J2") (pin "1") (pinfunction "1_1") (pintype "passive"))
      (node (ref "L7") (pin "2") (pinfunction "2_2") (pintype "passive"))
    )
    (net (code "32") (name "/PoC_D") (class "Default")
      (node (ref "C16") (pin "2") (pinfunction "2_2") (pintype "passive"))
      (node (ref "D35") (pin "5") (pinfunction "IO4_5") (pintype "bidirectional"))
      (node (ref "D35") (pin "6") (pinfunction "NC_6") (pintype "passive"))
      (node (ref "J2") (pin "2") (pinfunction "2_2") (pintype "passive"))
      (node (ref "L9") (pin "2") (pinfunction "2_2") (pintype "passive"))
    )
    (net (code "33") (name "/PoC_PWR") (class "Default")
      (node (ref "C121") (pin "1") (pinfunction "1_1") (pintype "passive"))
      (node (ref "C122") (pin "1") (pinfunction "1_1") (pintype "passive"))
      (node (ref "C123") (pin "1") (pinfunction "1_1") (pintype "passive"))
      (node (ref "C124") (pin "1") (pinfunction "1_1") (pintype "passive"))
      (node (ref "L2") (pin "1") (pinfunction "1_1") (pintype "passive"))
      (node (ref "L4") (pin "1") (pinfunction "1_1") (pintype "passive"))
      (node (ref "L6") (pin "1") (pinfunction "1_1") (pintype "passive"))
      (node (ref "L8") (pin "1") (pinfunction "1_1") (pintype "passive"))
      (node (ref "R24") (pin "1") (pinfunction "1_1") (pintype "passive"))
      (node (ref "R26") (pin "1") (pinfunction "1_1") (pintype "passive"))
      (node (ref "R27") (pin "1") (pinfunction "1_1") (pintype "passive"))
      (node (ref "R29") (pin "1") (pinfunction "1_1") (pintype "passive"))
    )
    (net (code "34") (name "/SIOA_N") (class "Default")
      (node (ref "C12") (pin "1") (pinfunction "1_1") (pintype "passive"))
      (node (ref "U1") (pin "22") (pinfunction "SIOAN_22") (pintype "bidirectional"))
    )
    (net (code "35") (name "/SIOA_P") (class "Default")
      (node (ref "C7") (pin "1") (pinfunction "1_1") (pintype "passive"))
      (node (ref "U1") (pin "23") (pinfunction "SIOAP_23") (pintype "bidirectional"))
    )
    (net (code "36") (name "/SIOB_N") (class "Default")
      (node (ref "C13") (pin "1") (pinfunction "1_1") (pintype "passive"))
      (node (ref "U1") (pin "19") (pinfunction "SIOBN_19") (pintype "bidirectional"))
    )
    (net (code "37") (name "/SIOB_P") (class "Default")
      (node (ref "C8") (pin "1") (pinfunction "1_1") (pintype "passive"))
      (node (ref "U1") (pin "18") (pinfunction "SIOBP_18") (pintype "bidirectional"))
    )
    (net (code "38") (name "/SIOC_N") (class "Default")
      (node (ref "C17") (pin "1") (pinfunction "1_1") (pintype "passive"))
      (node (ref "U1") (pin "9") (pinfunction "SIOCN_9") (pintype "bidirectional"))
    )
    (net (code "39") (name "/SIOC_P") (class "Default")
      (node (ref "C15") (pin "1") (pinfunction "1_1") (pintype "passive"))
      (node (ref "U1") (pin "10") (pinfunction "SIOCP_10") (pintype "bidirectional"))
    )
    (net (code "40") (name "/SIOD_N") (class "Default")
      (node (ref "C18") (pin "1") (pinfunction "1_1") (pintype "passive"))
      (node (ref "U1") (pin "6") (pinfunction "SIODN_6") (pintype "bidirectional"))
    )
    (net (code "41") (name "/SIOD_P") (class "Default")
      (node (ref "C16") (pin "1") (pinfunction "1_1") (pintype "passive"))
      (node (ref "U1") (pin "5") (pinfunction "SIODP_5") (pintype "bidirectional"))
    )
    (net (code "42") (name "/X25_N") (class "Default")
      (node (ref "C20") (pin "1") (pinfunction "1_1") (pintype "passive"))
      (node (ref "U1") (pin "16") (pinfunction "X2_16") (pintype "passive"))
      (node (ref "Y1") (pin "3") (pinfunction "3_3") (pintype "passive"))
    )
    (net (code "43") (name "/X25_P") (class "Default")
      (node (ref "C19") (pin "1") (pinfunction "1_1") (pintype "passive"))
      (node (ref "U1") (pin "15") (pinfunction "X1/OSC_15") (pintype "passive"))
      (node (ref "Y1") (pin "1") (pinfunction "1_1") (pintype "passive"))
    )
    (net (code "44") (name "/XRES") (class "Default")
      (node (ref "R20") (pin "2") (pinfunction "2_2") (pintype "passive"))
      (node (ref "U1") (pin "17") (pinfunction "XRES_17") (pintype "passive"))
    )
    (net (code "45") (name "/nPWDN") (class "Default")
      (node (ref "R14") (pin "2") (pinfunction "2_2") (pintype "passive"))
    )
    (net (code "46") (name "2V_AUX") (class "Default")
      (node (ref "C42") (pin "2") (pinfunction "2_2") (pintype "passive"))
      (node (ref "C43") (pin "2") (pinfunction "2_2") (pintype "passive"))
      (node (ref "U2") (pin "3") (pinfunction "VIN_3") (pintype "power_in"))
      (node (ref "U3") (pin "3") (pinfunction "VIN_3") (pintype "power_in"))
    )
    (net (code "47") (name "3V3") (class "Default")
      (node (ref "C33") (pin "1") (pinfunction "1_1") (pintype "passive"))
      (node (ref "C34") (pin "2") (pinfunction "2_2") (pintype "passive"))
      (node (ref "R12") (pin "2") (pinfunction "2_2") (pintype "passive"))
      (node (ref "R13") (pin "2") (pinfunction "2_2") (pintype "passive"))
      (node (ref "R17") (pin "2") (pinfunction "2_2") (pintype "passive"))
      (node (ref "R21") (pin "2") (pinfunction "2_2") (pintype "passive"))
      (node (ref "R9") (pin "2") (pinfunction "2_2") (pintype "passive"))
      (node (ref "U1") (pin "24") (pinfunction "VDDIO_24") (pintype "power_in"))
    )
    (net (code "48") (name "GND") (class "Default")
      (node (ref "C121") (pin "2") (pinfunction "2_2") (pintype "passive"))
      (node (ref "C122") (pin "2") (pinfunction "2_2") (pintype "passive"))
      (node (ref "C123") (pin "2") (pinfunction "2_2") (pintype "passive"))
      (node (ref "C124") (pin "2") (pinfunction "2_2") (pintype "passive"))
      (node (ref "C19") (pin "2") (pinfunction "2_2") (pintype "passive"))
      (node (ref "C20") (pin "2") (pinfunction "2_2") (pintype "passive"))
      (node (ref "C21") (pin "2") (pinfunction "2_2") (pintype "passive"))
      (node (ref "C22") (pin "1") (pinfunction "1_1") (pintype "passive"))
      (node (ref "C23") (pin "2") (pinfunction "2_2") (pintype "passive"))
      (node (ref "C24") (pin "1") (pinfunction "1_1") (pintype "passive"))
      (node (ref "C25") (pin "2") (pinfunction "2_2") (pintype "passive"))
      (node (ref "C26") (pin "1") (pinfunction "1_1") (pintype "passive"))
      (node (ref "C27") (pin "2") (pinfunction "2_2") (pintype "passive"))
      (node (ref "C28") (pin "1") (pinfunction "1_1") (pintype "passive"))
      (node (ref "C29") (pin "2") (pinfunction "2_2") (pintype "passive"))
      (node (ref "C30") (pin "1") (pinfunction "1_1") (pintype "passive"))
      (node (ref "C31") (pin "2") (pinfunction "2_2") (pintype "passive"))
      (node (ref "C32") (pin "1") (pinfunction "1_1") (pintype "passive"))
      (node (ref "C33") (pin "2") (pinfunction "2_2") (pintype "passive"))
      (node (ref "C34") (pin "1") (pinfunction "1_1") (pintype "passive"))
      (node (ref "C35") (pin "2") (pinfunction "2_2") (pintype "passive"))
      (node (ref "C36") (pin "1") (pinfunction "1_1") (pintype "passive"))
      (node (ref "C40") (pin "2") (pinfunction "2_2") (pintype "passive"))
      (node (ref "C41") (pin "2") (pinfunction "2_2") (pintype "passive"))
      (node (ref "C42") (pin "1") (pinfunction "1_1") (pintype "passive"))
      (node (ref "C43") (pin "1") (pinfunction "1_1") (pintype "passive"))
      (node (ref "D22") (pin "3") (pinfunction "GND_3") (pintype "power_in"))
      (node (ref "D22") (pin "8") (pinfunction "GND_8") (pintype "power_in"))
      (node (ref "D23") (pin "3") (pinfunction "GND_3") (pintype "power_in"))
      (node (ref "D23") (pin "8") (pinfunction "GND_8") (pintype "power_in"))
      (node (ref "D34") (pin "3") (pinfunction "GND_3") (pintype "power_in"))
      (node (ref "D34") (pin "8") (pinfunction "GND_8") (pintype "power_in"))
      (node (ref "D35") (pin "3") (pinfunction "GND_3") (pintype "power_in"))
      (node (ref "D35") (pin "8") (pinfunction "GND_8") (pintype "power_in"))
      (node (ref "J2") (pin "MH1") (pinfunction "MH1_MH1") (pintype "passive"))
      (node (ref "J2") (pin "MH2") (pinfunction "MH2_MH2") (pintype "passive"))
      (node (ref "J2") (pin "MH3") (pinfunction "MH3_MH3") (pintype "passive"))
      (node (ref "J2") (pin "MH4") (pinfunction "MH4_MH4") (pintype "passive"))
      (node (ref "J2") (pin "MH5") (pinfunction "MH5_MH5") (pintype "passive"))
      (node (ref "R10") (pin "1") (pinfunction "1_1") (pintype "passive"))
      (node (ref "R11") (pin "1") (pinfunction "1_1") (pintype "passive"))
      (node (ref "R15") (pin "1") (pinfunction "1_1") (pintype "passive"))
      (node (ref "R16") (pin "1") (pinfunction "1_1") (pintype "passive"))
      (node (ref "R18") (pin "1") (pinfunction "1_1") (pintype "passive"))
      (node (ref "R19") (pin "1") (pinfunction "1_1") (pintype "passive"))
      (node (ref "R20") (pin "1") (pinfunction "1_1") (pintype "passive"))
      (node (ref "U1") (pin "57") (pinfunction "GND_57") (pintype "power_in"))
      (node (ref "U2") (pin "1") (pinfunction "GND_1") (pintype "power_in"))
      (node (ref "U3") (pin "1") (pinfunction "GND_1") (pintype "power_in"))
      (node (ref "Y1") (pin "2") (pinfunction "GND_2") (pintype "power_in"))
      (node (ref "Y1") (pin "4") (pinfunction "GND_4") (pintype "power_in"))
    )
    (net (code "49") (name "Net-(C12-Pad2)") (class "Default")
      (node (ref "C12") (pin "2") (pinfunction "2_2") (pintype "passive"))
      (node (ref "R10") (pin "2") (pinfunction "2_2") (pintype "passive"))
    )
    (net (code "50") (name "Net-(C13-Pad2)") (class "Default")
      (node (ref "C13") (pin "2") (pinfunction "2_2") (pintype "passive"))
      (node (ref "R11") (pin "2") (pinfunction "2_2") (pintype "passive"))
    )
    (net (code "51") (name "Net-(C17-Pad2)") (class "Default")
      (node (ref "C17") (pin "2") (pinfunction "2_2") (pintype "passive"))
      (node (ref "R18") (pin "2") (pinfunction "2_2") (pintype "passive"))
    )
    (net (code "52") (name "Net-(C18-Pad2)") (class "Default")
      (node (ref "C18") (pin "2") (pinfunction "2_2") (pintype "passive"))
      (node (ref "R19") (pin "2") (pinfunction "2_2") (pintype "passive"))
    )
    (net (code "53") (name "Net-(C21-Pad1)") (class "Default")
      (node (ref "C21") (pin "1") (pinfunction "1_1") (pintype "passive"))
      (node (ref "C22") (pin "2") (pinfunction "2_2") (pintype "passive"))
      (node (ref "U1") (pin "8") (pinfunction "CAP_VDD_8") (pintype "power_in"))
    )
    (net (code "54") (name "Net-(C23-Pad1)") (class "Default")
      (node (ref "C23") (pin "1") (pinfunction "1_1") (pintype "passive"))
      (node (ref "C24") (pin "2") (pinfunction "2_2") (pintype "passive"))
      (node (ref "U1") (pin "20") (pinfunction "CAP_VDD_20") (pintype "power_in"))
    )
    (net (code "55") (name "Net-(L2-Pad2)") (class "Default")
      (node (ref "L2") (pin "2") (pinfunction "2_2") (pintype "passive"))
      (node (ref "L3") (pin "1") (pinfunction "1_1") (pintype "passive"))
      (node (ref "R24") (pin "2") (pinfunction "2_2") (pintype "passive"))
    )
    (net (code "56") (name "Net-(L4-Pad2)") (class "Default")
      (node (ref "L4") (pin "2") (pinfunction "2_2") (pintype "passive"))
      (node (ref "L5") (pin "1") (pinfunction "1_1") (pintype "passive"))
      (node (ref "R26") (pin "2") (pinfunction "2_2") (pintype "passive"))
    )
    (net (code "57") (name "Net-(L6-Pad2)") (class "Default")
      (node (ref "L6") (pin "2") (pinfunction "2_2") (pintype "passive"))
      (node (ref "L7") (pin "1") (pinfunction "1_1") (pintype "passive"))
      (node (ref "R27") (pin "2") (pinfunction "2_2") (pintype "passive"))
    )
    (net (code "58") (name "Net-(L8-Pad2)") (class "Default")
      (node (ref "L8") (pin "2") (pinfunction "2_2") (pintype "passive"))
      (node (ref "L9") (pin "1") (pinfunction "1_1") (pintype "passive"))
      (node (ref "R29") (pin "2") (pinfunction "2_2") (pintype "passive"))
    )
    (net (code "59") (name "Net-(U1A-CFG0)") (class "Default")
      (node (ref "R13") (pin "1") (pinfunction "1_1") (pintype "passive"))
      (node (ref "R16") (pin "2") (pinfunction "2_2") (pintype "passive"))
      (node (ref "U1") (pin "4") (pinfunction "CFG0_4") (pintype "input"))
    )
    (net (code "60") (name "Net-(U1A-CFG1{slash}MFP6)") (class "Default")
      (node (ref "R12") (pin "1") (pinfunction "1_1") (pintype "passive"))
      (node (ref "R15") (pin "2") (pinfunction "2_2") (pintype "passive"))
      (node (ref "U1") (pin "25") (pinfunction "CFG1/MFP6_25") (pintype "bidirectional"))
    )
    (net (code "61") (name "Net-(U1A-PWDNB)") (class "Default")
      (node (ref "R14") (pin "1") (pinfunction "1_1") (pintype "passive"))
      (node (ref "R9") (pin "1") (pinfunction "1_1") (pintype "passive"))
      (node (ref "U1") (pin "11") (pinfunction "PWDNB_11") (pintype "input"))
    )
    (net (code "62") (name "unconnected-(D22-IO2-Pad2)") (class "Default")
      (node (ref "D22") (pin "2") (pinfunction "IO2_2") (pintype "bidirectional"))
    )
    (net (code "63") (name "unconnected-(D22-IO3-Pad4)") (class "Default")
      (node (ref "D22") (pin "4") (pinfunction "IO3_4") (pintype "bidirectional"))
    )
    (net (code "64") (name "unconnected-(D22-NC-Pad7)") (class "Default")
      (node (ref "D22") (pin "7") (pinfunction "NC_7") (pintype "passive"))
    )
    (net (code "65") (name "unconnected-(D22-NC-Pad9)") (class "Default")
      (node (ref "D22") (pin "9") (pinfunction "NC_9") (pintype "passive"))
    )
    (net (code "66") (name "unconnected-(D23-IO2-Pad2)") (class "Default")
      (node (ref "D23") (pin "2") (pinfunction "IO2_2") (pintype "bidirectional"))
    )
    (net (code "67") (name "unconnected-(D23-IO3-Pad4)") (class "Default")
      (node (ref "D23") (pin "4") (pinfunction "IO3_4") (pintype "bidirectional"))
    )
    (net (code "68") (name "unconnected-(D23-IO4-Pad5)") (class "Default")
      (node (ref "D23") (pin "5") (pinfunction "IO4_5") (pintype "bidirectional"))
    )
    (net (code "69") (name "unconnected-(D23-NC-Pad6)") (class "Default")
      (node (ref "D23") (pin "6") (pinfunction "NC_6") (pintype "passive"))
    )
    (net (code "70") (name "unconnected-(D23-NC-Pad7)") (class "Default")
      (node (ref "D23") (pin "7") (pinfunction "NC_7") (pintype "passive"))
    )
    (net (code "71") (name "unconnected-(D23-NC-Pad9)") (class "Default")
      (node (ref "D23") (pin "9") (pinfunction "NC_9") (pintype "passive"))
    )
    (net (code "72") (name "unconnected-(D34-IO1-Pad1)") (class "Default")
      (node (ref "D34") (pin "1") (pinfunction "IO1_1") (pintype "bidirectional"))
    )
    (net (code "73") (name "unconnected-(D34-IO2-Pad2)") (class "Default")
      (node (ref "D34") (pin "2") (pinfunction "IO2_2") (pintype "bidirectional"))
    )
    (net (code "74") (name "unconnected-(D34-IO3-Pad4)") (class "Default")
      (node (ref "D34") (pin "4") (pinfunction "IO3_4") (pintype "bidirectional"))
    )
    (net (code "75") (name "unconnected-(D34-NC-Pad7)") (class "Default")
      (node (ref "D34") (pin "7") (pinfunction "NC_7") (pintype "passive"))
    )
    (net (code "76") (name "unconnected-(D34-NC-Pad9)") (class "Default")
      (node (ref "D34") (pin "9") (pinfunction "NC_9") (pintype "passive"))
    )
    (net (code "77") (name "unconnected-(D34-NC-Pad10)") (class "Default")
      (node (ref "D34") (pin "10") (pinfunction "NC_10") (pintype "passive"))
    )
    (net (code "78") (name "unconnected-(D35-IO1-Pad1)") (class "Default")
      (node (ref "D35") (pin "1") (pinfunction "IO1_1") (pintype "bidirectional"))
    )
    (net (code "79") (name "unconnected-(D35-IO2-Pad2)") (class "Default")
      (node (ref "D35") (pin "2") (pinfunction "IO2_2") (pintype "bidirectional"))
    )
    (net (code "80") (name "unconnected-(D35-IO3-Pad4)") (class "Default")
      (node (ref "D35") (pin "4") (pinfunction "IO3_4") (pintype "bidirectional"))
    )
    (net (code "81") (name "unconnected-(D35-NC-Pad7)") (class "Default")
      (node (ref "D35") (pin "7") (pinfunction "NC_7") (pintype "passive"))
    )
    (net (code "82") (name "unconnected-(D35-NC-Pad9)") (class "Default")
      (node (ref "D35") (pin "9") (pinfunction "NC_9") (pintype "passive"))
    )
    (net (code "83") (name "unconnected-(D35-NC-Pad10)") (class "Default")
      (node (ref "D35") (pin "10") (pinfunction "NC_10") (pintype "passive"))
    )
    (net (code "84") (name "unconnected-(U1A-MFP0-Pad1)") (class "Default")
      (node (ref "U1") (pin "1") (pinfunction "MFP0_1") (pintype "bidirectional+no_connect"))
    )
    (net (code "85") (name "unconnected-(U1A-MFP1-Pad2)") (class "Default")
      (node (ref "U1") (pin "2") (pinfunction "MFP1_2") (pintype "bidirectional+no_connect"))
    )
    (net (code "86") (name "unconnected-(U1A-MFP2-Pad3)") (class "Default")
      (node (ref "U1") (pin "3") (pinfunction "MFP2_3") (pintype "bidirectional+no_connect"))
    )
    (net (code "87") (name "unconnected-(U1A-MFP3-Pad12)") (class "Default")
      (node (ref "U1") (pin "12") (pinfunction "MFP3_12") (pintype "bidirectional+no_connect"))
    )
    (net (code "88") (name "unconnected-(U1A-MFP4-Pad13)") (class "Default")
      (node (ref "U1") (pin "13") (pinfunction "MFP4_13") (pintype "bidirectional+no_connect"))
    )
    (net (code "89") (name "unconnected-(U1A-MFP5-Pad14)") (class "Default")
      (node (ref "U1") (pin "14") (pinfunction "MFP5_14") (pintype "bidirectional+no_connect"))
    )
    (net (code "90") (name "unconnected-(U1A-SCL1{slash}MFP8-Pad27)") (class "Default")
      (node (ref "U1") (pin "27") (pinfunction "SCL1/MFP8_27") (pintype "bidirectional+no_connect"))
    )
    (net (code "91") (name "unconnected-(U1A-SDA1{slash}MFP7-Pad26)") (class "Default")
      (node (ref "U1") (pin "26") (pinfunction "SDA1/MFP7_26") (pintype "bidirectional+no_connect"))
    )
    (net (code "92") (name "unconnected-(U1B-NC-Pad43)") (class "Default")
      (node (ref "U1") (pin "43") (pinfunction "NC_43") (pintype "passive+no_connect"))
    )
    (net (code "93") (name "unconnected-(U1B-NC-Pad44)") (class "Default")
      (node (ref "U1") (pin "44") (pinfunction "NC_44") (pintype "passive+no_connect"))
    )
    (net (code "94") (name "unconnected-(U1B-NC-Pad45)") (class "Default")
      (node (ref "U1") (pin "45") (pinfunction "NC_45") (pintype "passive+no_connect"))
    )
    (net (code "95") (name "unconnected-(U1B-NC-Pad46)") (class "Default")
      (node (ref "U1") (pin "46") (pinfunction "NC_46") (pintype "passive+no_connect"))
    )
    (net (code "96") (name "unconnected-(U1B-NC-Pad47)") (class "Default")
      (node (ref "U1") (pin "47") (pinfunction "NC_47") (pintype "passive+no_connect"))
    )
    (net (code "97") (name "unconnected-(U1B-NC-Pad48)") (class "Default")
      (node (ref "U1") (pin "48") (pinfunction "NC_48") (pintype "passive+no_connect"))
    )
    (net (code "98") (name "unconnected-(U1B-NC-Pad49)") (class "Default")
      (node (ref "U1") (pin "49") (pinfunction "NC_49") (pintype "passive+no_connect"))
    )
    (net (code "99") (name "unconnected-(U1B-NC-Pad50)") (class "Default")
      (node (ref "U1") (pin "50") (pinfunction "NC_50") (pintype "passive+no_connect"))
    )
    (net (code "100") (name "unconnected-(U1B-NC-Pad51)") (class "Default")
      (node (ref "U1") (pin "51") (pinfunction "NC_51") (pintype "passive+no_connect"))
    )
    (net (code "101") (name "unconnected-(U1B-NC-Pad52)") (class "Default")
      (node (ref "U1") (pin "52") (pinfunction "NC_52") (pintype "passive+no_connect"))
    )
    (net (code "102") (name "unconnected-(U1B-NC-Pad53)") (class "Default")
      (node (ref "U1") (pin "53") (pinfunction "NC_53") (pintype "passive+no_connect"))
    )
    (net (code "103") (name "unconnected-(U1B-NC-Pad54)") (class "Default")
      (node (ref "U1") (pin "54") (pinfunction "NC_54") (pintype "passive+no_connect"))
    )
  )
)
